# PowerSupply.net
KiCad netlist of a schematic drawn in Altium Designer
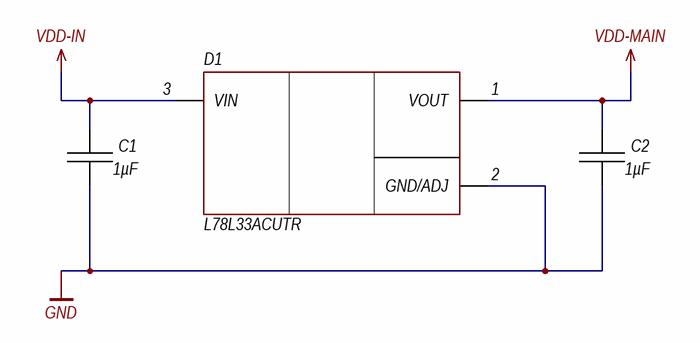
[diagram p0: PowerSupply.SchDoc]

(export (version "E")
  (design (tool "Eeschema 10.0.6"))
  (components
    (comp (ref "C1") (value "1µF") (footprint "CH0603CM") (libsource (lib "Discrete") (part "Capacitor")))
    (comp (ref "C2") (value "1µF") (footprint "CH0603CM") (libsource (lib "Discrete") (part "Capacitor")))
    (comp (ref "D1")
      (value "L78L33ACUTR")
      (footprint "SOT89_123")
      (description "LDO")
      (fields (field (name "MANUFACTURER") "ST Microelectronics"))
      (libsource (lib "Power Supplies") (part "L78LxxACUTR"))
    )
  )
  (nets
    (net (code "1") (name "GND") (class "Default")
      (node (ref "C1") (pin "1") (pinfunction "1_1") (pintype "passive"))
      (node (ref "C2") (pin "1") (pinfunction "1_1") (pintype "passive"))
      (node (ref "D1") (pin "2") (pinfunction "GND/ADJ_2") (pintype "power_in"))
    )
    (net (code "2") (name "VDD-IN") (class "Default")
      (node (ref "C1") (pin "2") (pinfunction "2_2") (pintype "passive"))
      (node (ref "D1") (pin "3") (pinfunction "VIN_3") (pintype "power_in"))
    )
    (net (code "3") (name "VDD-MAIN") (class "Default")
      (node (ref "C2") (pin "2") (pinfunction "2_2") (pintype "passive"))
      (node (ref "D1") (pin "1") (pinfunction "VOUT_1") (pintype "power_in"))
    )
  )
)
